# IoT_wall_1plug.net
KiCad netlist of a schematic drawn in EAGLE
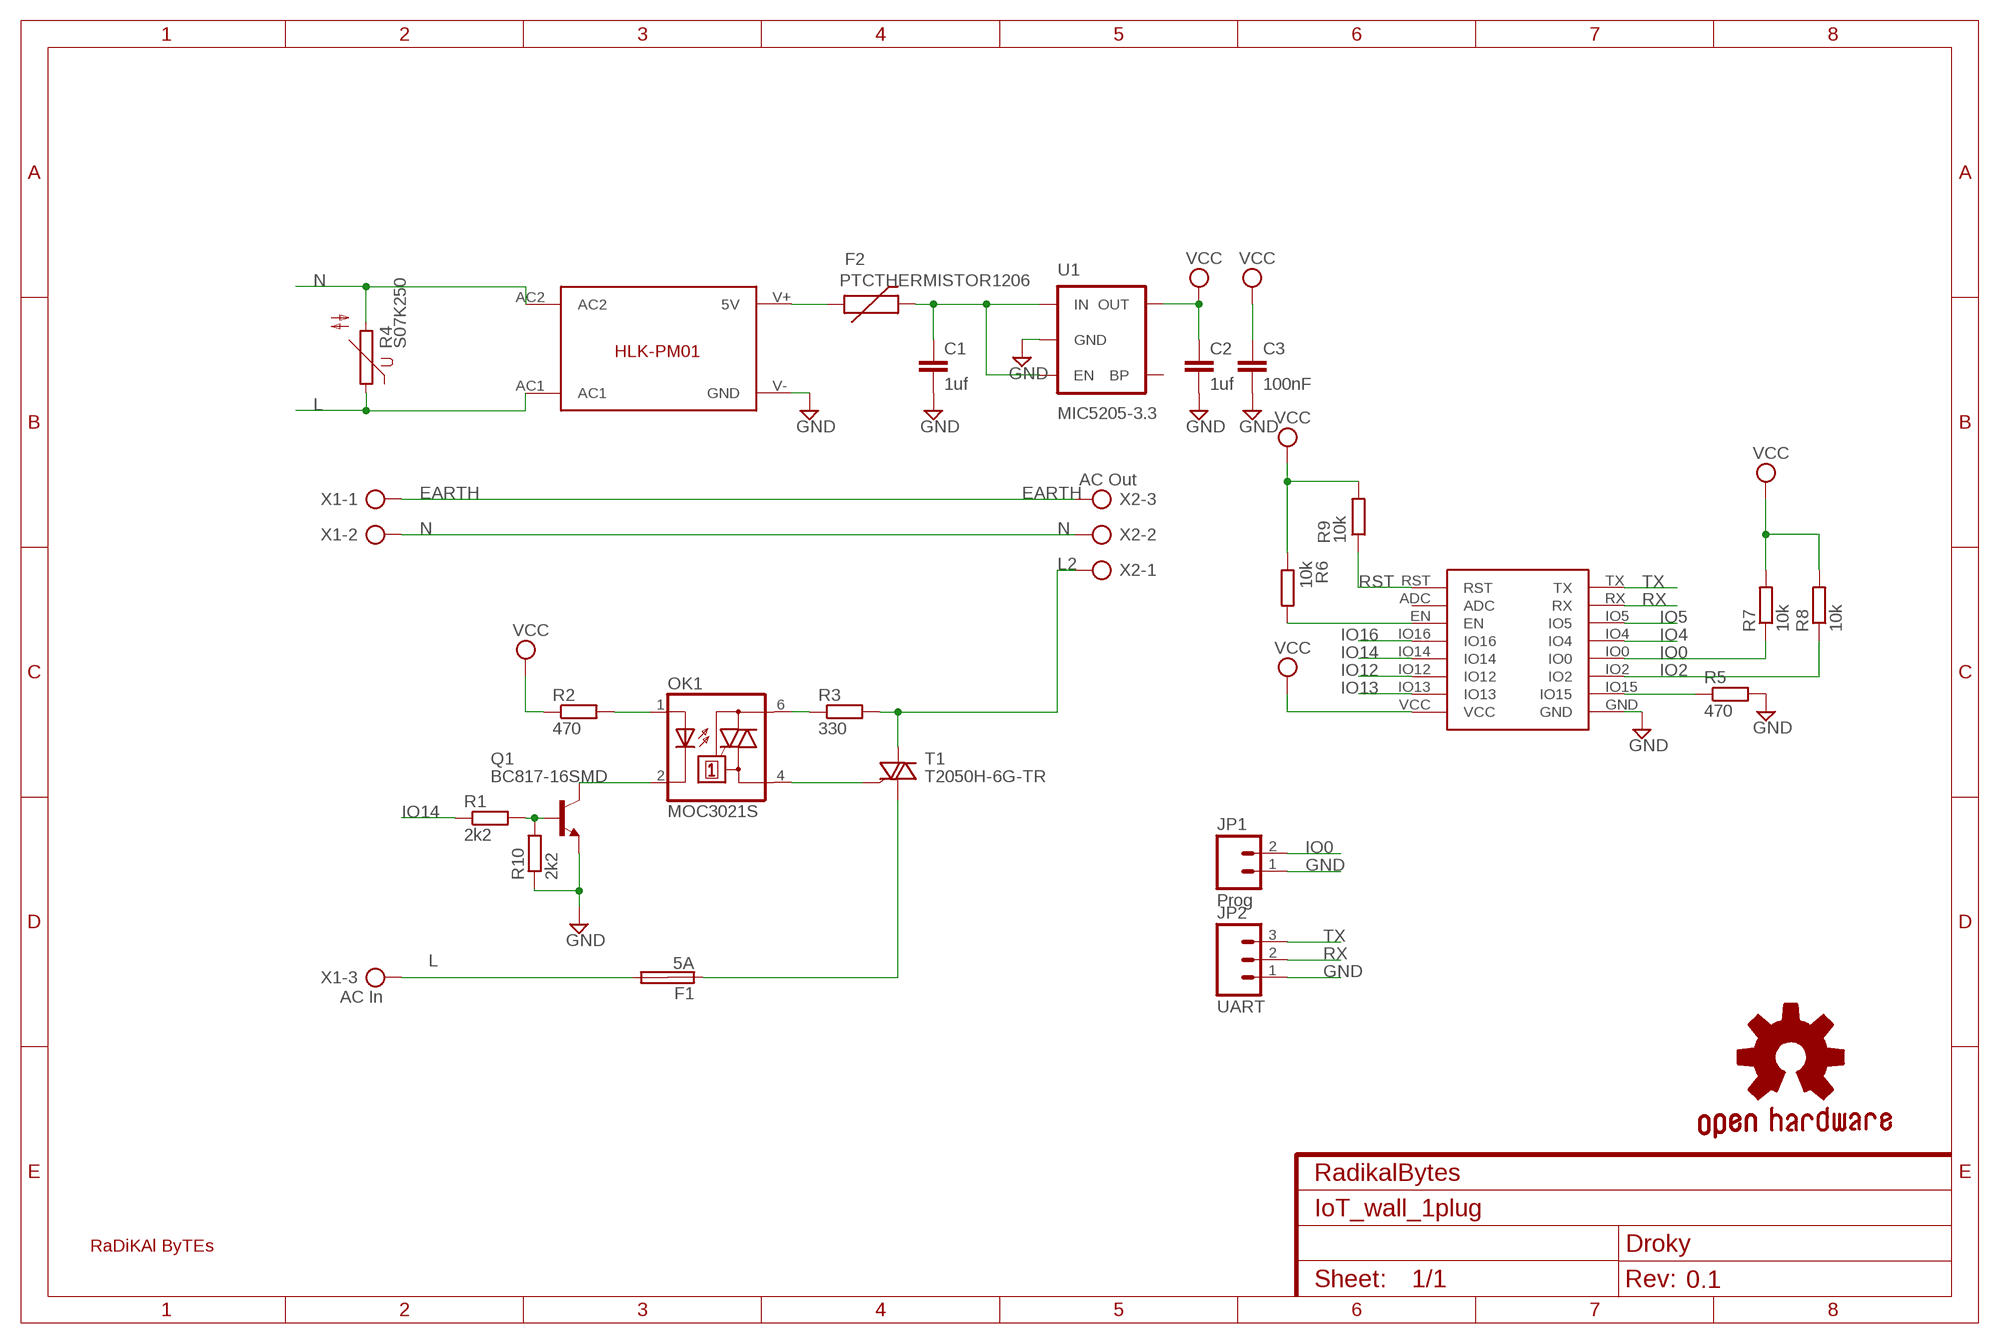
[diagram p0: schematic, sheet 1]

(export (version "E")
  (design (tool "Eeschema 10.0.6"))
  (components
    (comp (ref "C1")
      (value "1uf")
      (footprint "eagle-import:RCL_C0805K")
      (libsource (lib "eagle-import") (part "RCL_C-EUC0805K"))
    )
    (comp (ref "C2")
      (value "1uf")
      (footprint "eagle-import:RCL_C0805K")
      (libsource (lib "eagle-import") (part "RCL_C-EUC0805K"))
    )
    (comp (ref "C3")
      (value "100nF")
      (footprint "eagle-import:RCL_C0805K")
      (libsource (lib "eagle-import") (part "RCL_C-EUC0805K"))
    )
    (comp (ref "F1")
      (value "5A")
      (footprint "eagle-import:SHK20Q")
      (libsource (lib "eagle-import") (part "SHK20Q"))
    )
    (comp (ref "F2")
      (value "PTCTHERMISTOR1206")
      (footprint "eagle-import:SPARKFUN-POWERIC_PTC-1206")
      (libsource (lib "eagle-import") (part "SPARKFUN-POWERIC_PTCTHERMISTOR1206"))
    )
    (comp (ref "GOLD_ORB_SM1")
      (value "OSHWLOGO_GOLD_ORB_MED")
      (footprint "eagle-import:OSHW1")
      (libsource (lib "eagle-import") (part "OSHWLOGO_GOLD_ORB_MED"))
    )
    (comp (ref "JP1")
      (value "Prog")
      (footprint "eagle-import:SPARKFUN-CONNECTORS_1X02")
      (libsource (lib "eagle-import") (part "SPARKFUN-CONNECTORS_M02PTH"))
    )
    (comp (ref "JP2")
      (value "UART")
      (footprint "eagle-import:SPARKFUN-CONNECTORS_1X03")
      (libsource (lib "eagle-import") (part "SPARKFUN-CONNECTORS_M03PTH"))
    )
    (comp (ref "OK1")
      (value "MOC3021S")
      (footprint "eagle-import:DIL6-SMD")
      (fields (field (name "MF") "FAIRCHILD SEMICONDUCTOR") (field (name "MPN") "MOC3031SM"))
      (libsource (lib "eagle-import") (part "MOC30S31"))
    )
    (comp (ref "Q1")
      (value "BC817-16SMD")
      (footprint "eagle-import:SOT23-BEC")
      (libsource (lib "eagle-import") (part "BC817SMD-16"))
    )
    (comp (ref "R1")
      (value "2k2")
      (footprint "eagle-import:R0805")
      (libsource (lib "eagle-import") (part "R-EU_R0805"))
    )
    (comp (ref "R2")
      (value "470")
      (footprint "eagle-import:R0805")
      (libsource (lib "eagle-import") (part "R-EU_R0805"))
    )
    (comp (ref "R3")
      (value "330")
      (footprint "eagle-import:R0805")
      (libsource (lib "eagle-import") (part "R-EU_R0805"))
    )
    (comp (ref "R4")
      (value "S07K250")
      (footprint "eagle-import:S07K250")
      (libsource (lib "eagle-import") (part "S07K250"))
    )
    (comp (ref "R5")
      (value "470")
      (footprint "eagle-import:R0805")
      (libsource (lib "eagle-import") (part "R-EU_R0805"))
    )
    (comp (ref "R6")
      (value "10k")
      (footprint "eagle-import:R0805")
      (libsource (lib "eagle-import") (part "R-EU_R0805"))
    )
    (comp (ref "R7")
      (value "10k")
      (footprint "eagle-import:R0805")
      (libsource (lib "eagle-import") (part "R-EU_R0805"))
    )
    (comp (ref "R8")
      (value "10k")
      (footprint "eagle-import:R0805")
      (libsource (lib "eagle-import") (part "R-EU_R0805"))
    )
    (comp (ref "R9")
      (value "10k")
      (footprint "eagle-import:R0805")
      (libsource (lib "eagle-import") (part "R-EU_R0805"))
    )
    (comp (ref "R10")
      (value "2k2")
      (footprint "eagle-import:R0805")
      (libsource (lib "eagle-import") (part "R-EU_R0805"))
    )
    (comp (ref "T1")
      (value "T2050H-6G-TR")
      (footprint "eagle-import:D2PAK-3")
      (libsource (lib "eagle-import") (part "BT136D2PACK"))
    )
    (comp (ref "U$1")
      (value "HLK-PM01")
      (footprint "eagle-import:HLK-PM01")
      (libsource (lib "eagle-import") (part "HLK-PM01"))
    )
    (comp (ref "U$2")
      (value "DAVLIB_ESP8266")
      (footprint "eagle-import:DAVLIB_ESP8266")
      (libsource (lib "eagle-import") (part "DAVLIB_ESP8266"))
    )
    (comp (ref "U$4")
      (value "MI_LOGO1.5MM")
      (footprint "eagle-import:MI_LOGO_PEQUEÑO")
      (libsource (lib "eagle-import") (part "MI_LOGO1.5MM"))
    )
    (comp (ref "U1")
      (value "MIC5205-3.3")
      (footprint "eagle-import:SPARKFUN-POWERIC_SOT23-5")
      (libsource (lib "eagle-import") (part "SPARKFUN-POWERIC_V_REG_MIC52053.3V"))
    )
    (comp (ref "X1")
      (value "AC In")
      (footprint "eagle-import:AK500_3")
      (libsource (lib "eagle-import") (part "AK500/3"))
    )
    (comp (ref "X2")
      (value "AC Out")
      (footprint "eagle-import:AK500_3")
      (libsource (lib "eagle-import") (part "AK500/3"))
    )
  )
  (nets
    (net (code "1") (name "/EARTH") (class "Default")
      (node (ref "X1") (pin "1") (pinfunction "KL_1") (pintype "passive"))
      (node (ref "X2") (pin "3") (pinfunction "KL_3") (pintype "passive"))
    )
    (net (code "2") (name "/IO0") (class "Default")
      (node (ref "JP1") (pin "2") (pinfunction "2_2") (pintype "passive"))
      (node (ref "R7") (pin "1") (pinfunction "1_1") (pintype "passive"))
      (node (ref "U$2") (pin "IO0") (pinfunction "IO0_IO0") (pintype "bidirectional"))
    )
    (net (code "3") (name "/IO2") (class "Default")
      (node (ref "R8") (pin "1") (pinfunction "1_1") (pintype "passive"))
      (node (ref "U$2") (pin "IO2") (pinfunction "IO2_IO2") (pintype "bidirectional"))
    )
    (net (code "4") (name "/IO4") (class "Default")
      (node (ref "U$2") (pin "IO4") (pinfunction "IO4_IO4") (pintype "bidirectional"))
    )
    (net (code "5") (name "/IO5") (class "Default")
      (node (ref "U$2") (pin "IO5") (pinfunction "IO5_IO5") (pintype "bidirectional"))
    )
    (net (code "6") (name "/IO12") (class "Default")
      (node (ref "U$2") (pin "IO12") (pinfunction "IO12_IO12") (pintype "bidirectional"))
    )
    (net (code "7") (name "/IO13") (class "Default")
      (node (ref "U$2") (pin "IO13") (pinfunction "IO13_IO13") (pintype "bidirectional"))
    )
    (net (code "8") (name "/IO14") (class "Default")
      (node (ref "R1") (pin "1") (pinfunction "1_1") (pintype "passive"))
      (node (ref "U$2") (pin "IO14") (pinfunction "IO14_IO14") (pintype "bidirectional"))
    )
    (net (code "9") (name "/IO16") (class "Default")
      (node (ref "U$2") (pin "IO16") (pinfunction "IO16_IO16") (pintype "bidirectional"))
    )
    (net (code "10") (name "/L") (class "Default")
      (node (ref "F1") (pin "2A") (pinfunction "2A_2A") (pintype "passive"))
      (node (ref "R4") (pin "1") (pinfunction "1_1") (pintype "passive"))
      (node (ref "U$1") (pin "AC1") (pinfunction "AC1_AC1") (pintype "bidirectional"))
      (node (ref "X1") (pin "3") (pinfunction "KL_3") (pintype "passive"))
    )
    (net (code "11") (name "/L2") (class "Default")
      (node (ref "R3") (pin "2") (pinfunction "2_2") (pintype "passive"))
      (node (ref "T1") (pin "4") (pinfunction "A2_4") (pintype "passive"))
      (node (ref "X2") (pin "1") (pinfunction "KL_1") (pintype "passive"))
    )
    (net (code "12") (name "/N") (class "Default")
      (node (ref "R4") (pin "2") (pinfunction "2_2") (pintype "passive"))
      (node (ref "U$1") (pin "AC2") (pinfunction "AC2_AC2") (pintype "bidirectional"))
      (node (ref "X1") (pin "2") (pinfunction "KL_2") (pintype "passive"))
      (node (ref "X2") (pin "2") (pinfunction "KL_2") (pintype "passive"))
    )
    (net (code "13") (name "/RST") (class "Default")
      (node (ref "R9") (pin "1") (pinfunction "1_1") (pintype "passive"))
      (node (ref "U$2") (pin "RST") (pinfunction "RST_RST") (pintype "bidirectional"))
    )
    (net (code "14") (name "/RX") (class "Default")
      (node (ref "JP2") (pin "2") (pinfunction "2_2") (pintype "passive"))
      (node (ref "U$2") (pin "RX") (pinfunction "RX_RX") (pintype "bidirectional"))
    )
    (net (code "15") (name "/TX") (class "Default")
      (node (ref "JP2") (pin "3") (pinfunction "3_3") (pintype "passive"))
      (node (ref "U$2") (pin "TX") (pinfunction "TX_TX") (pintype "bidirectional"))
    )
    (net (code "16") (name "GND") (class "Default")
      (node (ref "C1") (pin "2") (pinfunction "2_2") (pintype "passive"))
      (node (ref "C2") (pin "2") (pinfunction "2_2") (pintype "passive"))
      (node (ref "C3") (pin "2") (pinfunction "2_2") (pintype "passive"))
      (node (ref "JP1") (pin "1") (pinfunction "1_1") (pintype "passive"))
      (node (ref "JP2") (pin "1") (pinfunction "1_1") (pintype "passive"))
      (node (ref "Q1") (pin "E") (pinfunction "E_E") (pintype "passive"))
      (node (ref "R10") (pin "1") (pinfunction "1_1") (pintype "passive"))
      (node (ref "R5") (pin "2") (pinfunction "2_2") (pintype "passive"))
      (node (ref "U$1") (pin "V-") (pinfunction "GND_V-") (pintype "bidirectional"))
      (node (ref "U$2") (pin "GND") (pinfunction "GND_GND") (pintype "bidirectional"))
      (node (ref "U1") (pin "2") (pinfunction "GND_2") (pintype "input"))
    )
    (net (code "17") (name "Net-(OK1-A)") (class "Default")
      (node (ref "OK1") (pin "1") (pinfunction "A_1") (pintype "passive"))
      (node (ref "R2") (pin "2") (pinfunction "2_2") (pintype "passive"))
    )
    (net (code "18") (name "Net-(OK1-A1)") (class "Default")
      (node (ref "OK1") (pin "4") (pinfunction "A1_4") (pintype "passive"))
      (node (ref "T1") (pin "3") (pinfunction "G_3") (pintype "passive"))
    )
    (net (code "19") (name "Net-(OK1-A2)") (class "Default")
      (node (ref "OK1") (pin "6") (pinfunction "A2_6") (pintype "passive"))
      (node (ref "R3") (pin "1") (pinfunction "1_1") (pintype "passive"))
    )
    (net (code "20") (name "Net-(OK1-C)") (class "Default")
      (node (ref "OK1") (pin "2") (pinfunction "C_2") (pintype "passive"))
      (node (ref "Q1") (pin "C") (pinfunction "C_C") (pintype "passive"))
    )
    (net (code "21") (name "Net-(Q1-PadB)") (class "Default")
      (node (ref "Q1") (pin "B") (pinfunction "B_B") (pintype "passive"))
      (node (ref "R1") (pin "2") (pinfunction "2_2") (pintype "passive"))
      (node (ref "R10") (pin "2") (pinfunction "2_2") (pintype "passive"))
    )
    (net (code "22") (name "Net-(R5-Pad1)") (class "Default")
      (node (ref "R5") (pin "1") (pinfunction "1_1") (pintype "passive"))
      (node (ref "U$2") (pin "IO15") (pinfunction "IO15_IO15") (pintype "bidirectional"))
    )
    (net (code "23") (name "Net-(R6-Pad2)") (class "Default")
      (node (ref "R6") (pin "2") (pinfunction "2_2") (pintype "passive"))
      (node (ref "U$2") (pin "EN") (pinfunction "EN_EN") (pintype "bidirectional"))
    )
    (net (code "24") (name "Net-(T1-A1)") (class "Default")
      (node (ref "F1") (pin "1A") (pinfunction "1A_1A") (pintype "passive"))
      (node (ref "T1") (pin "1") (pinfunction "A1_1") (pintype "passive"))
    )
    (net (code "25") (name "Net-(U$1-5V)") (class "Default")
      (node (ref "F2") (pin "1") (pinfunction "1_1") (pintype "bidirectional"))
      (node (ref "U$1") (pin "V+") (pinfunction "5V_V+") (pintype "bidirectional"))
    )
    (net (code "26") (name "Net-(U1-EN)") (class "Default")
      (node (ref "C1") (pin "1") (pinfunction "1_1") (pintype "passive"))
      (node (ref "F2") (pin "2") (pinfunction "2_2") (pintype "bidirectional"))
      (node (ref "U1") (pin "1") (pinfunction "IN_1") (pintype "input"))
      (node (ref "U1") (pin "3") (pinfunction "EN_3") (pintype "input"))
    )
    (net (code "27") (name "VCC") (class "Default")
      (node (ref "C2") (pin "1") (pinfunction "1_1") (pintype "passive"))
      (node (ref "C3") (pin "1") (pinfunction "1_1") (pintype "passive"))
      (node (ref "R2") (pin "1") (pinfunction "1_1") (pintype "passive"))
      (node (ref "R6") (pin "1") (pinfunction "1_1") (pintype "passive"))
      (node (ref "R7") (pin "2") (pinfunction "2_2") (pintype "passive"))
      (node (ref "R8") (pin "2") (pinfunction "2_2") (pintype "passive"))
      (node (ref "R9") (pin "2") (pinfunction "2_2") (pintype "passive"))
      (node (ref "U$2") (pin "VCC") (pinfunction "VCC_VCC") (pintype "bidirectional"))
      (node (ref "U1") (pin "5") (pinfunction "OUT_5") (pintype "passive"))
    )
    (net (code "28") (name "unconnected-(F1-Pad1B)") (class "Default")
      (node (ref "F1") (pin "1B") (pinfunction "1B_1B") (pintype "passive"))
    )
    (net (code "29") (name "unconnected-(F1-Pad2B)") (class "Default")
      (node (ref "F1") (pin "2B") (pinfunction "2B_2B") (pintype "passive"))
    )
    (net (code "30") (name "unconnected-(U$2-PadADC)") (class "Default")
      (node (ref "U$2") (pin "ADC") (pinfunction "ADC_ADC") (pintype "bidirectional"))
    )
    (net (code "31") (name "unconnected-(U1-BP-Pad4)") (class "Default")
      (node (ref "U1") (pin "4") (pinfunction "BP_4") (pintype "input"))
    )
  )
)
